# LB_BIT_w21_SUM-v03_2_0x.net
KiCad netlist of a schematic drawn in EAGLE
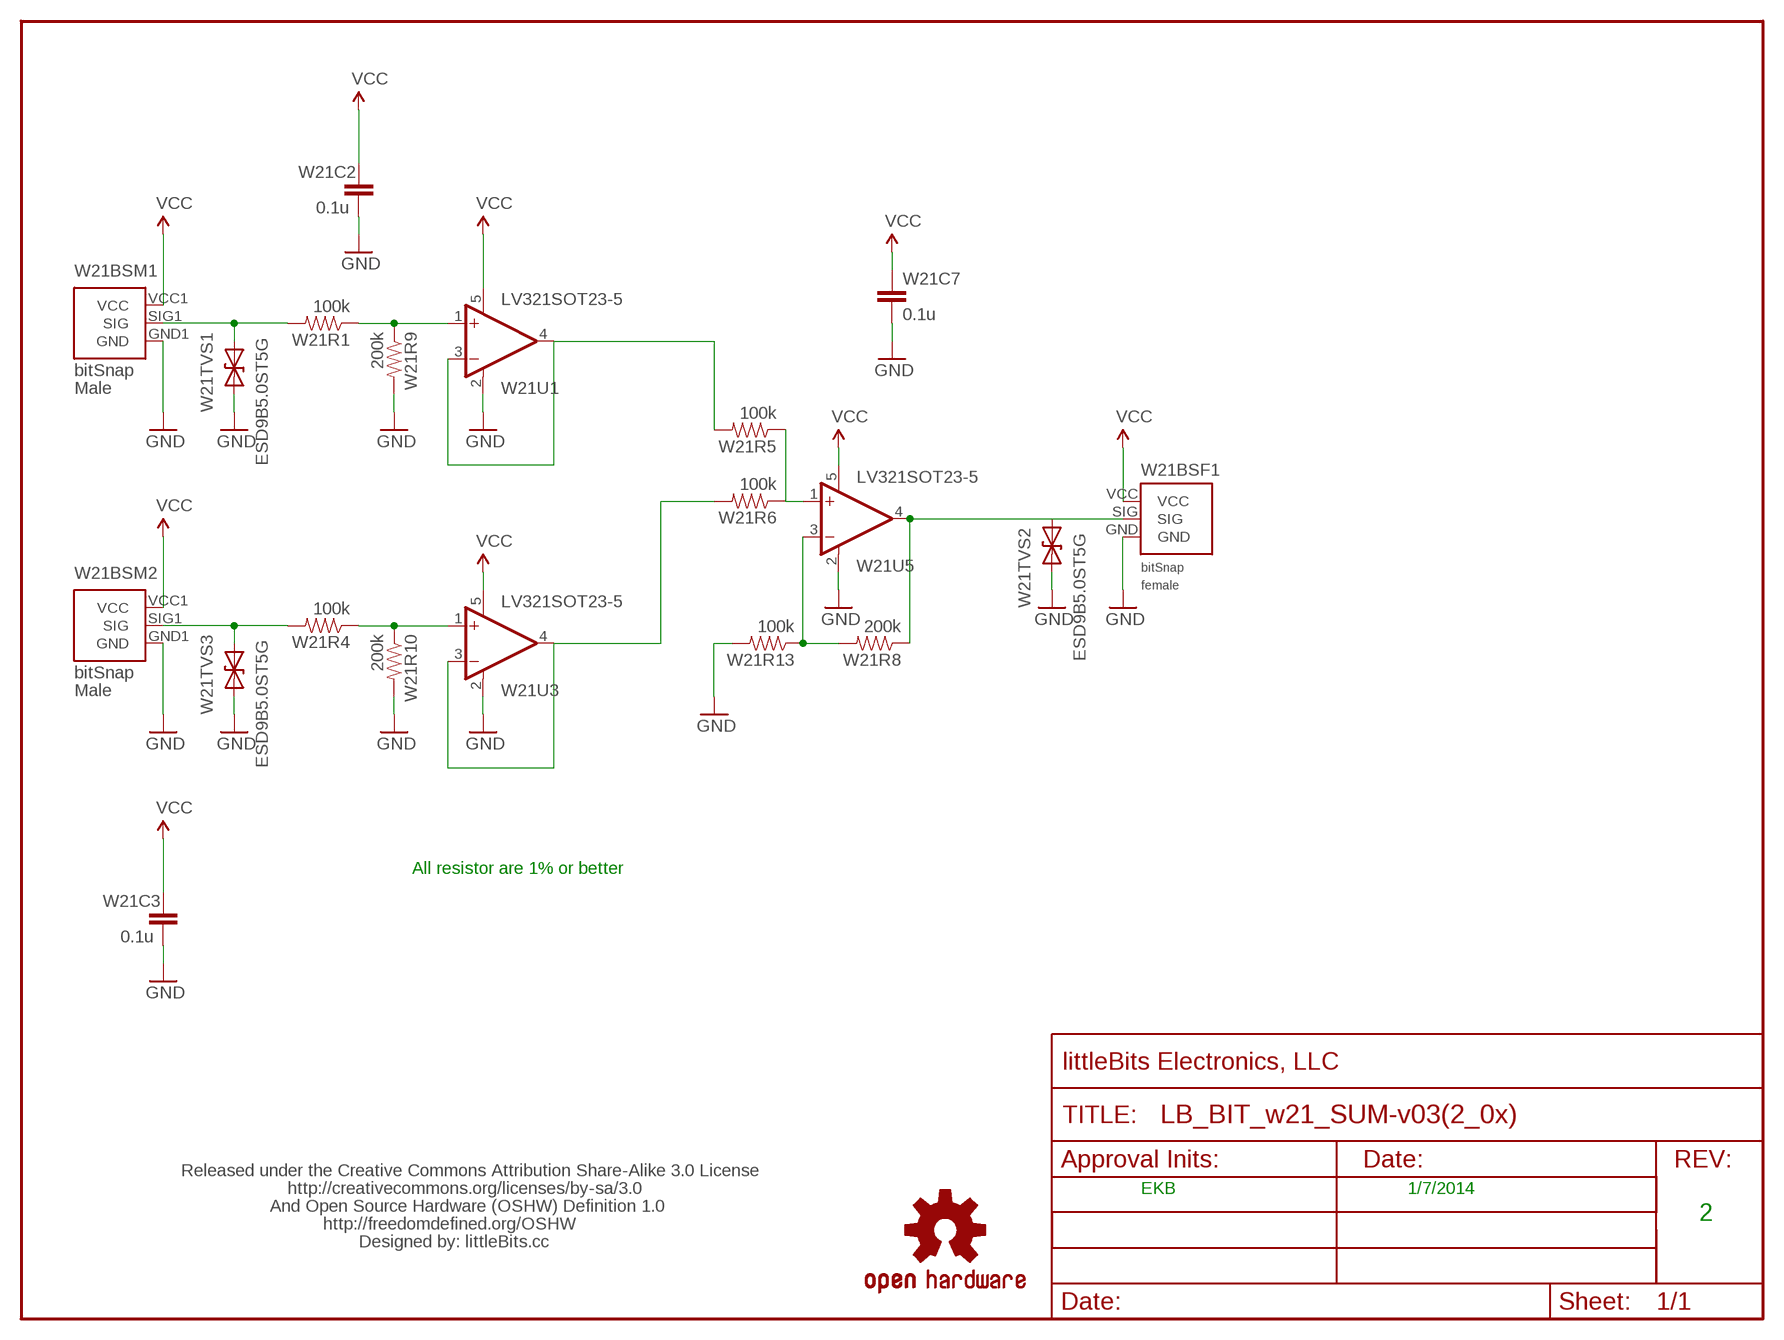
[diagram p0: schematic, sheet 1]

(export (version "E")
  (design (tool "Eeschema 10.0.6"))
  (components
    (comp (ref "FRAME1")
      (value "FRAME-LETTER")
      (footprint "eagle-import:FABDWG01")
      (libsource (lib "eagle-import") (part "FRAME-LETTER"))
    )
    (comp (ref "U$1")
      (value "OSHWCREDIT")
      (footprint "eagle-import:OSHWCREDIT")
      (libsource (lib "eagle-import") (part "OSHWCREDIT"))
    )
    (comp (ref "U$2")
      (value "OSHW-LOGOL")
      (footprint "eagle-import:OSHW-LOGO-L")
      (libsource (lib "eagle-import") (part "OSHW-LOGOL"))
    )
    (comp (ref "W21BSF1")
      (value "BITSNAP_V03_FEMALE")
      (footprint "eagle-import:BITSNAP_V03_FEMALE")
      (libsource (lib "eagle-import") (part "BITSNAP_V03_FEMALE"))
    )
    (comp (ref "W21BSM1")
      (value "BITSNAP_V03_MALE")
      (footprint "eagle-import:BITSNAP_V03_MALE")
      (libsource (lib "eagle-import") (part "BITSNAP_V03_MALE"))
    )
    (comp (ref "W21BSM2")
      (value "BITSNAP_V03_MALE")
      (footprint "eagle-import:BITSNAP_V03_MALE")
      (libsource (lib "eagle-import") (part "BITSNAP_V03_MALE"))
    )
    (comp (ref "W21C2")
      (value "0.1u")
      (footprint "eagle-import:CAP-0603")
      (libsource (lib "eagle-import") (part "CAPCAP-0603"))
    )
    (comp (ref "W21C3")
      (value "0.1u")
      (footprint "eagle-import:CAP-0603")
      (libsource (lib "eagle-import") (part "CAPCAP-0603"))
    )
    (comp (ref "W21C7")
      (value "0.1u")
      (footprint "eagle-import:CAP-0603")
      (libsource (lib "eagle-import") (part "CAPCAP-0603"))
    )
    (comp (ref "W21R1")
      (value "100k")
      (footprint "eagle-import:RES-0603")
      (libsource (lib "eagle-import") (part "RESISTOR0603"))
    )
    (comp (ref "W21R4")
      (value "100k")
      (footprint "eagle-import:RES-0603")
      (libsource (lib "eagle-import") (part "RESISTOR0603"))
    )
    (comp (ref "W21R5")
      (value "100k")
      (footprint "eagle-import:RES-0603")
      (libsource (lib "eagle-import") (part "RESISTOR0603"))
    )
    (comp (ref "W21R6")
      (value "100k")
      (footprint "eagle-import:RES-0603")
      (libsource (lib "eagle-import") (part "RESISTOR0603"))
    )
    (comp (ref "W21R8")
      (value "200k")
      (footprint "eagle-import:RES-0603")
      (libsource (lib "eagle-import") (part "RESISTOR0603"))
    )
    (comp (ref "W21R9")
      (value "200k")
      (footprint "eagle-import:RES-0603")
      (libsource (lib "eagle-import") (part "RESISTOR0603"))
    )
    (comp (ref "W21R10")
      (value "200k")
      (footprint "eagle-import:RES-0603")
      (libsource (lib "eagle-import") (part "RESISTOR0603"))
    )
    (comp (ref "W21R13")
      (value "100k")
      (footprint "eagle-import:RES-0603")
      (libsource (lib "eagle-import") (part "RESISTOR0603"))
    )
    (comp (ref "W21TVS1")
      (value "ESD9B5.0ST5G")
      (footprint "eagle-import:SOD-923")
      (libsource (lib "eagle-import") (part "DIODE-TVSSOD-923"))
    )
    (comp (ref "W21TVS2")
      (value "ESD9B5.0ST5G")
      (footprint "eagle-import:SOD-923")
      (libsource (lib "eagle-import") (part "DIODE-TVSSOD-923"))
    )
    (comp (ref "W21TVS3")
      (value "ESD9B5.0ST5G")
      (footprint "eagle-import:SOD-923")
      (libsource (lib "eagle-import") (part "DIODE-TVSSOD-923"))
    )
    (comp (ref "W21U1")
      (value "LV321SOT23-5")
      (footprint "eagle-import:SOT23-5")
      (libsource (lib "eagle-import") (part "LV321SOT23-5"))
    )
    (comp (ref "W21U3")
      (value "LV321SOT23-5")
      (footprint "eagle-import:SOT23-5")
      (libsource (lib "eagle-import") (part "LV321SOT23-5"))
    )
    (comp (ref "W21U5")
      (value "LV321SOT23-5")
      (footprint "eagle-import:SOT23-5")
      (libsource (lib "eagle-import") (part "LV321SOT23-5"))
    )
  )
  (nets
    (net (code "1") (name "GND") (class "Default")
      (node (ref "W21BSF1") (pin "GND") (pinfunction "GND_GND") (pintype "bidirectional"))
      (node (ref "W21BSM1") (pin "GND1") (pinfunction "GND_GND1") (pintype "bidirectional"))
      (node (ref "W21BSM2") (pin "GND1") (pinfunction "GND_GND1") (pintype "bidirectional"))
      (node (ref "W21C2") (pin "2") (pinfunction "2_2") (pintype "passive"))
      (node (ref "W21C3") (pin "2") (pinfunction "2_2") (pintype "passive"))
      (node (ref "W21C7") (pin "2") (pinfunction "2_2") (pintype "passive"))
      (node (ref "W21R10") (pin "2") (pinfunction "2_2") (pintype "passive"))
      (node (ref "W21R13") (pin "2") (pinfunction "2_2") (pintype "passive"))
      (node (ref "W21R9") (pin "2") (pinfunction "2_2") (pintype "passive"))
      (node (ref "W21TVS1") (pin "1") (pinfunction "A_1") (pintype "passive"))
      (node (ref "W21TVS2") (pin "1") (pinfunction "A_1") (pintype "passive"))
      (node (ref "W21TVS3") (pin "1") (pinfunction "A_1") (pintype "passive"))
      (node (ref "W21U1") (pin "2") (pinfunction "V-_2") (pintype "power_in"))
      (node (ref "W21U3") (pin "2") (pinfunction "V-_2") (pintype "power_in"))
      (node (ref "W21U5") (pin "2") (pinfunction "V-_2") (pintype "power_in"))
    )
    (net (code "2") (name "Net-(W21BSM1-SIG)") (class "Default")
      (node (ref "W21BSM1") (pin "SIG1") (pinfunction "SIG_SIG1") (pintype "bidirectional"))
      (node (ref "W21R1") (pin "2") (pinfunction "2_2") (pintype "passive"))
      (node (ref "W21TVS1") (pin "2") (pinfunction "C_2") (pintype "passive"))
    )
    (net (code "3") (name "Net-(W21BSM2-SIG)") (class "Default")
      (node (ref "W21BSM2") (pin "SIG1") (pinfunction "SIG_SIG1") (pintype "bidirectional"))
      (node (ref "W21R4") (pin "2") (pinfunction "2_2") (pintype "passive"))
      (node (ref "W21TVS3") (pin "2") (pinfunction "C_2") (pintype "passive"))
    )
    (net (code "4") (name "Net-(W21TVS2-C)") (class "Default")
      (node (ref "W21BSF1") (pin "SIG") (pinfunction "SIG_SIG") (pintype "bidirectional"))
      (node (ref "W21R8") (pin "1") (pinfunction "1_1") (pintype "passive"))
      (node (ref "W21TVS2") (pin "2") (pinfunction "C_2") (pintype "passive"))
      (node (ref "W21U5") (pin "4") (pinfunction "OUT_4") (pintype "output"))
    )
    (net (code "5") (name "Net-(W21U1-+IN)") (class "Default")
      (node (ref "W21R1") (pin "1") (pinfunction "1_1") (pintype "passive"))
      (node (ref "W21R9") (pin "1") (pinfunction "1_1") (pintype "passive"))
      (node (ref "W21U1") (pin "1") (pinfunction "+IN_1") (pintype "input"))
    )
    (net (code "6") (name "Net-(W21U1--IN)") (class "Default")
      (node (ref "W21R5") (pin "2") (pinfunction "2_2") (pintype "passive"))
      (node (ref "W21U1") (pin "3") (pinfunction "-IN_3") (pintype "input"))
      (node (ref "W21U1") (pin "4") (pinfunction "OUT_4") (pintype "output"))
    )
    (net (code "7") (name "Net-(W21U3-+IN)") (class "Default")
      (node (ref "W21R10") (pin "1") (pinfunction "1_1") (pintype "passive"))
      (node (ref "W21R4") (pin "1") (pinfunction "1_1") (pintype "passive"))
      (node (ref "W21U3") (pin "1") (pinfunction "+IN_1") (pintype "input"))
    )
    (net (code "8") (name "Net-(W21U3--IN)") (class "Default")
      (node (ref "W21R6") (pin "2") (pinfunction "2_2") (pintype "passive"))
      (node (ref "W21U3") (pin "3") (pinfunction "-IN_3") (pintype "input"))
      (node (ref "W21U3") (pin "4") (pinfunction "OUT_4") (pintype "output"))
    )
    (net (code "9") (name "Net-(W21U5-+IN)") (class "Default")
      (node (ref "W21R5") (pin "1") (pinfunction "1_1") (pintype "passive"))
      (node (ref "W21R6") (pin "1") (pinfunction "1_1") (pintype "passive"))
      (node (ref "W21U5") (pin "1") (pinfunction "+IN_1") (pintype "input"))
    )
    (net (code "10") (name "Net-(W21U5--IN)") (class "Default")
      (node (ref "W21R13") (pin "1") (pinfunction "1_1") (pintype "passive"))
      (node (ref "W21R8") (pin "2") (pinfunction "2_2") (pintype "passive"))
      (node (ref "W21U5") (pin "3") (pinfunction "-IN_3") (pintype "input"))
    )
    (net (code "11") (name "VCC") (class "Default")
      (node (ref "W21BSF1") (pin "VCC") (pinfunction "VCC_VCC") (pintype "bidirectional"))
      (node (ref "W21BSM1") (pin "VCC1") (pinfunction "VCC_VCC1") (pintype "bidirectional"))
      (node (ref "W21BSM2") (pin "VCC1") (pinfunction "VCC_VCC1") (pintype "bidirectional"))
      (node (ref "W21C2") (pin "1") (pinfunction "1_1") (pintype "passive"))
      (node (ref "W21C3") (pin "1") (pinfunction "1_1") (pintype "passive"))
      (node (ref "W21C7") (pin "1") (pinfunction "1_1") (pintype "passive"))
      (node (ref "W21U1") (pin "5") (pinfunction "V+_5") (pintype "power_in"))
      (node (ref "W21U3") (pin "5") (pinfunction "V+_5") (pintype "power_in"))
      (node (ref "W21U5") (pin "5") (pinfunction "V+_5") (pintype "power_in"))
    )
  )
)
